# mspm0l1306.net
KiCad netlist of a schematic drawn in EasyEDA Pro
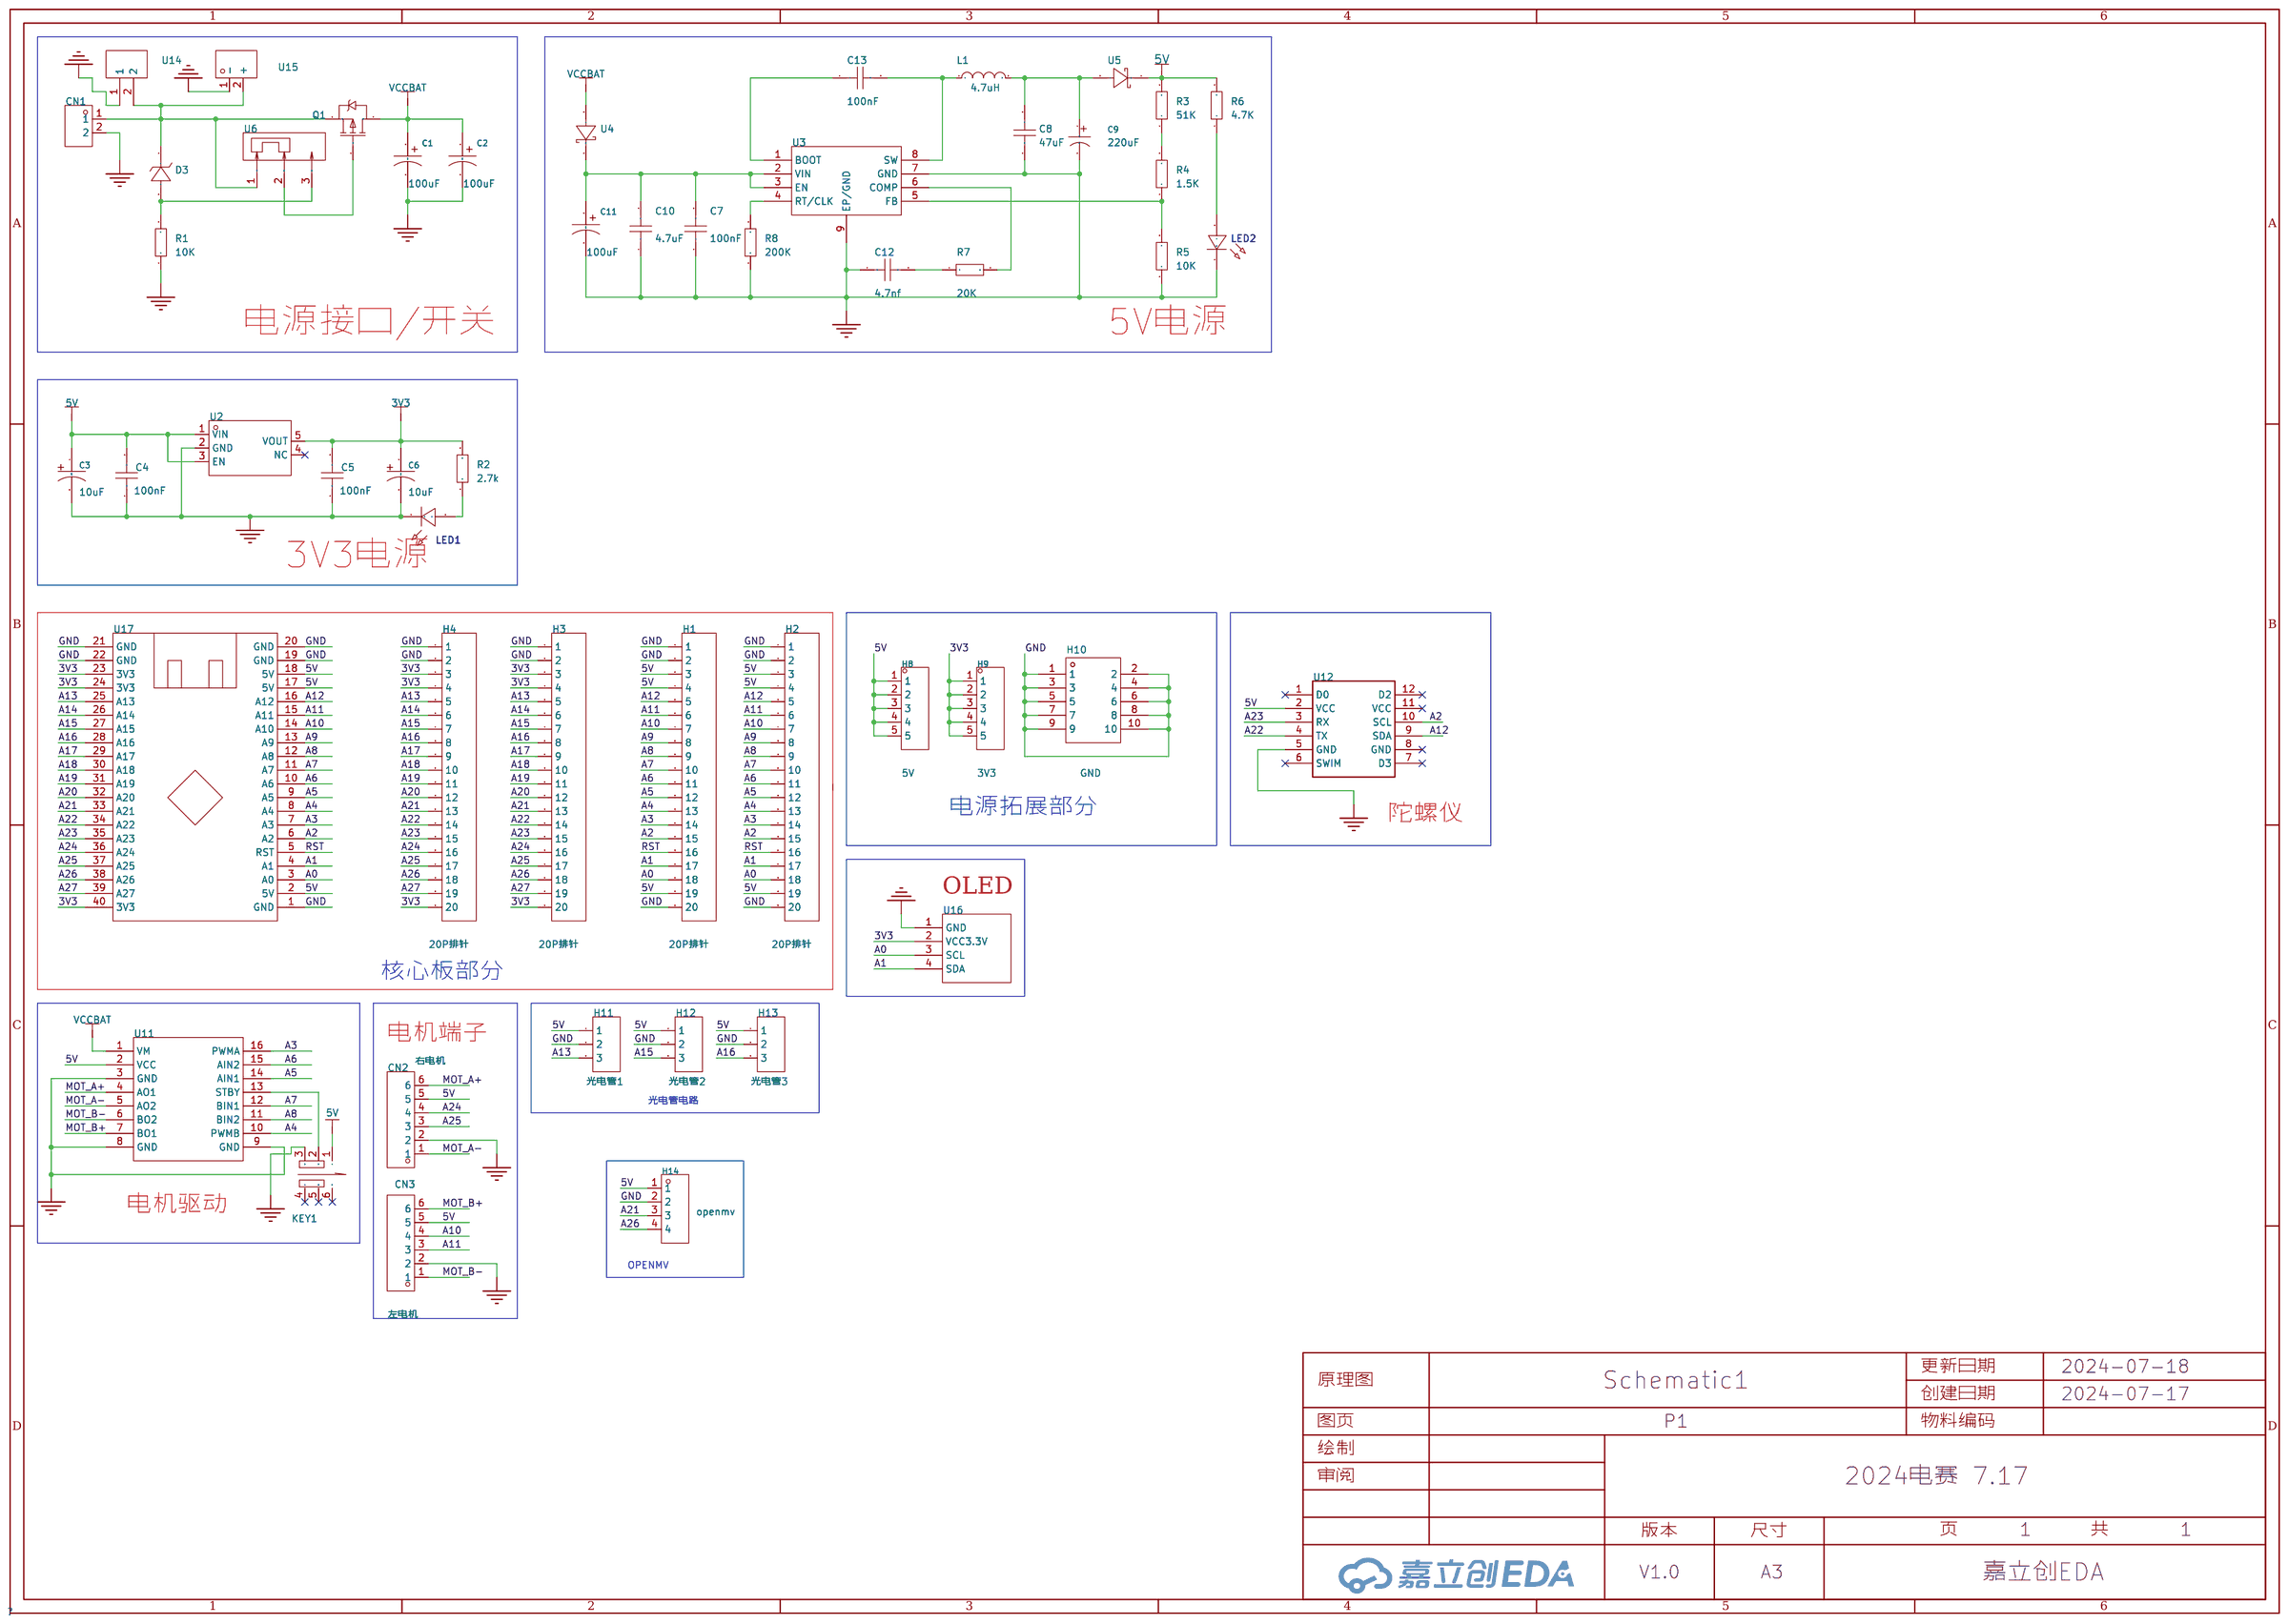
[diagram p0: schematic sheet]

(export (version "E")
  (design (tool "Eeschema 10.0.6"))
  (components
    (comp (ref "C1")
      (value "100uF")
      (fields
        (field (name "Manufacturer Part") "35YXF100MEFCTA8X11.5")
        (field (name "Manufacturer") "rubycon(红宝石)")
      )
      (libsource (lib "easyedapro") (part "35YXF100MEFCTA8X11.5"))
    )
    (comp (ref "C2")
      (value "100uF")
      (fields
        (field (name "Manufacturer Part") "35YXF100MEFCTA8X11.5")
        (field (name "Manufacturer") "rubycon(红宝石)")
      )
      (libsource (lib "easyedapro") (part "35YXF100MEFCTA8X11.5"))
    )
    (comp (ref "C3")
      (value "10uF")
      (footprint "easyedapro:CAP-TH_BD8.0-P3.50-D0.6-FD_1")
      (description "容值:10uF;精度:±20%;额定电压:250V;纹波电流:210mA@100kHz;等效串联电阻:10Ω@100kHz;")
      (fields (field (name "Manufacturer Part") "LKMD0902E100MF") (field (name "Manufacturer") "Ymin(永铭)"))
      (libsource (lib "easyedapro") (part "LKMD0902E100MF"))
    )
    (comp (ref "C4")
      (value "100nF")
      (footprint "easyedapro:C0805")
      (libsource (lib "easyedapro") (part "CapAcitance"))
    )
    (comp (ref "C5")
      (value "100nF")
      (footprint "easyedapro:C0805")
      (libsource (lib "easyedapro") (part "CapAcitance"))
    )
    (comp (ref "C6")
      (value "10uF")
      (footprint "easyedapro:CAP-TH_BD8.0-P3.50-D0.6-FD_1")
      (description "容值:10uF;精度:±20%;额定电压:250V;纹波电流:210mA@100kHz;等效串联电阻:10Ω@100kHz;")
      (fields (field (name "Manufacturer Part") "LKMD0902E100MF") (field (name "Manufacturer") "Ymin(永铭)"))
      (libsource (lib "easyedapro") (part "LKMD0902E100MF"))
    )
    (comp (ref "C7")
      (value "100nF")
      (footprint "easyedapro:C0805")
      (libsource (lib "easyedapro") (part "CapAcitance"))
    )
    (comp (ref "C8")
      (value "47uF")
      (footprint "easyedapro:C0805")
      (libsource (lib "easyedapro") (part "CapAcitance"))
    )
    (comp (ref "C9")
      (value "220uF")
      (fields
        (field (name "Manufacturer Part") "25RX30220M8X11.5")
        (field (name "Manufacturer") "rubycon(红宝石)")
      )
      (libsource (lib "easyedapro") (part "25RX30220M8X11.5"))
    )
    (comp (ref "C10")
      (value "4.7uF")
      (footprint "easyedapro:C0805")
      (libsource (lib "easyedapro") (part "CapAcitance"))
    )
    (comp (ref "C11")
      (value "100uF")
      (fields
        (field (name "Manufacturer Part") "35YXF100MEFCTA8X11.5")
        (field (name "Manufacturer") "rubycon(红宝石)")
      )
      (libsource (lib "easyedapro") (part "35YXF100MEFCTA8X11.5"))
    )
    (comp (ref "C12")
      (value "4.7nf")
      (footprint "easyedapro:C0805")
      (libsource (lib "easyedapro") (part "CapAcitance"))
    )
    (comp (ref "C13")
      (value "100nF")
      (footprint "easyedapro:C0805")
      (libsource (lib "easyedapro") (part "CapAcitance"))
    )
    (comp (ref "CN1")
      (value "XT30U-M")
      (fields (field (name "Manufacturer") "AMASS(艾迈斯)"))
      (libsource (lib "easyedapro") (part "XT30U-M"))
    )
    (comp (ref "CN2")
      (value "右电机")
      (footprint "easyedapro:CONN-TH_XH2.54-6P")
      (fields (field (name "Manufacturer Part") "XH2.54*6P_直插"))
      (libsource (lib "easyedapro") (part "XH2.54*6P_直插"))
    )
    (comp (ref "CN3")
      (value "左电机")
      (footprint "easyedapro:CONN-TH_XH2.54-6P")
      (fields (field (name "Manufacturer Part") "XH2.54*6P_直插"))
      (libsource (lib "easyedapro") (part "XH2.54*6P_直插"))
    )
    (comp (ref "D3")
      (value "BZT52C16")
      (footprint "easyedapro:SOD-123_L2.7-W1.6-LS3.7-RD")
      (description "稳压值(标称值):-;精度:-;功率:500mW;反向电流(Ir):100nA@11.2V;")
      (fields (field (name "Manufacturer") "Slkor(萨科微)"))
      (libsource (lib "easyedapro") (part "BZT52C16_C707145"))
    )
    (comp (ref "H1")
      (value "20P排针")
      (footprint "easyedapro:HDR-TH_20P-P2.54-V-F")
      (libsource (lib "easyedapro") (part "HDR-F_2.54_1x20P"))
    )
    (comp (ref "H2")
      (value "20P排针")
      (footprint "easyedapro:HDR-TH_20P-P2.54-V-F")
      (libsource (lib "easyedapro") (part "HDR-F_2.54_1x20P"))
    )
    (comp (ref "H3")
      (value "20P排针")
      (footprint "easyedapro:HDR-TH_20P-P2.54-V-F")
      (libsource (lib "easyedapro") (part "HDR-F_2.54_1x20P"))
    )
    (comp (ref "H4")
      (value "20P排针")
      (footprint "easyedapro:HDR-TH_20P-P2.54-V-F")
      (libsource (lib "easyedapro") (part "HDR-F_2.54_1x20P"))
    )
    (comp (ref "H8")
      (value "5V")
      (footprint "easyedapro:HDR-TH_5P-P2.54-V-M")
      (libsource (lib "easyedapro") (part "MTP125-1105S1"))
    )
    (comp (ref "H9")
      (value "3V3")
      (footprint "easyedapro:HDR-TH_5P-P2.54-V-M")
      (libsource (lib "easyedapro") (part "MTP125-1105S1"))
    )
    (comp (ref "H10")
      (value "GND")
      (footprint "easyedapro:HDR-TH_10P-P2.54-V-M-R2-C5-S2.54")
      (libsource (lib "easyedapro") (part "HDR-M-2.54_2x5"))
    )
    (comp (ref "H11")
      (value "光电管1")
      (footprint "easyedapro:HDR-F-2.54_1X3")
      (libsource (lib "easyedapro") (part "HDR-F-2.54_1x3"))
    )
    (comp (ref "H12")
      (value "光电管2")
      (footprint "easyedapro:HDR-F-2.54_1X3")
      (libsource (lib "easyedapro") (part "HDR-F-2.54_1x3"))
    )
    (comp (ref "H13")
      (value "光电管3")
      (footprint "easyedapro:HDR-F-2.54_1X3")
      (libsource (lib "easyedapro") (part "HDR-F-2.54_1x3"))
    )
    (comp (ref "H14")
      (value "openmv")
      (footprint "easyedapro:HDR-TH_4P-P2.54-V-F")
      (libsource (lib "easyedapro") (part "2.54-1*4P母"))
    )
    (comp (ref "KEY1")
      (value "自锁开关 5.8Z白灰白260G")
      (footprint "easyedapro:SW-TH_6P-L5.8-W5.8-P2.00-LS4.5-TR")
      (description "耐温260度")
      (libsource (lib "easyedapro") (part "Self-locking switch 5.8ZWhite and white260G"))
    )
    (comp (ref "L1")
      (value "4.7uH")
      (fields (field (name "Manufacturer Part") "PK0810-470MB") (field (name "Manufacturer") "SXN(顺翔诺)"))
      (libsource (lib "easyedapro") (part "PK0810-470MB"))
    )
    (comp (ref "LED1")
      (value "~")
      (footprint "easyedapro:LED_0805")
      (libsource (lib "easyedapro") (part "LED_G"))
    )
    (comp (ref "LED2")
      (value "~")
      (footprint "easyedapro:LED_0805")
      (libsource (lib "easyedapro") (part "LED_G"))
    )
    (comp (ref "Q1")
      (value "HY19P03D")
      (footprint "easyedapro:TO-252-2_L6.6-W6.1-P4.57-LS9.9-TL-CW")
      (fields (field (name "Manufacturer") "HUAYI(华羿微)"))
      (libsource (lib "easyedapro") (part "HY19P03D"))
    )
    (comp (ref "R1") (value "10K") (footprint "easyedapro:R0805") (libsource (lib "easyedapro") (part "电阻")))
    (comp (ref "R2") (value "2.7k") (footprint "easyedapro:R0805") (libsource (lib "easyedapro") (part "电阻")))
    (comp (ref "R3") (value "51K") (footprint "easyedapro:R0805") (libsource (lib "easyedapro") (part "电阻")))
    (comp (ref "R4") (value "1.5K") (footprint "easyedapro:R0805") (libsource (lib "easyedapro") (part "电阻")))
    (comp (ref "R5") (value "10K") (footprint "easyedapro:R0805") (libsource (lib "easyedapro") (part "电阻")))
    (comp (ref "R6") (value "4.7K") (footprint "easyedapro:R0805") (libsource (lib "easyedapro") (part "电阻")))
    (comp (ref "R7") (value "20K") (footprint "easyedapro:R0805") (libsource (lib "easyedapro") (part "电阻")))
    (comp (ref "R8") (value "200K") (footprint "easyedapro:R0805") (libsource (lib "easyedapro") (part "电阻")))
    (comp (ref "U2")
      (value "RT9013-3.3GB")
      (footprint "easyedapro:SOT-23-5_L2.9-W1.6-P0.94-LS2.8-BL")
      (libsource (lib "easyedapro") (part "RT9013-3.3GB"))
    )
    (comp (ref "U3")
      (value "~")
      (footprint "easyedapro:ESOP-8_L4.9-W3.9-P1.27-LS6.0-BL-EP3.1")
      (libsource (lib "easyedapro") (part "SP1N28STER"))
    )
    (comp (ref "U4")
      (value "SS54")
      (footprint "easyedapro:SMA_L4.2-W2.6-LS5.1-RD")
      (libsource (lib "easyedapro") (part "SS54_C9900023219"))
    )
    (comp (ref "U5")
      (value "SS54")
      (footprint "easyedapro:SMA_L4.2-W2.6-LS5.1-RD")
      (libsource (lib "easyedapro") (part "SS54_C9900023219"))
    )
    (comp (ref "U6")
      (value "SS-12D10-G5")
      (footprint "easyedapro:SW-TH_SS-12D10-G050")
      (fields (field (name "Manufacturer") "DEALON(德艺隆)"))
      (libsource (lib "easyedapro") (part "SS-12D10-G5"))
    )
    (comp (ref "U11")
      (value "~")
      (footprint "easyedapro:TB6612")
      (description "STBY/VCC接3.3V\nVM接小于12V")
      (libsource (lib "easyedapro") (part "TB6612模块"))
    )
    (comp (ref "U12")
      (value "MPU6050(JY6X)")
      (footprint "easyedapro:维特陀螺仪")
      (libsource (lib "easyedapro") (part "维特陀螺仪"))
    )
    (comp (ref "U14") (value "~") (footprint "easyedapro:T插头") (libsource (lib "easyedapro") (part "T插头")))
    (comp (ref "U15")
      (value "XT60")
      (footprint "easyedapro:CONN-TH_XT60")
      (description "模型锂电连接器 XT60-M")
      (fields (field (name "Manufacturer") "AMASS(艾迈斯)"))
      (libsource (lib "easyedapro") (part "XT60"))
    )
    (comp (ref "U16") (value "~") (libsource (lib "easyedapro") (part "OLED_4P")))
    (comp (ref "U17")
      (value "~")
      (footprint "easyedapro:MspM0L1306")
      (libsource (lib "easyedapro") (part "MspM0L1306核心板"))
    )
  )
  (nets
    (net (code "1") (name "/A0") (class "Default")
      (node (ref "H1") (pin "18") (pinfunction "18_18") (pintype "input"))
      (node (ref "H2") (pin "18") (pinfunction "18_18") (pintype "input"))
      (node (ref "U16") (pin "3") (pinfunction "SCL_3") (pintype "input"))
      (node (ref "U17") (pin "3") (pinfunction "A0_3") (pintype "input"))
    )
    (net (code "2") (name "/A1") (class "Default")
      (node (ref "H1") (pin "17") (pinfunction "17_17") (pintype "input"))
      (node (ref "H2") (pin "17") (pinfunction "17_17") (pintype "input"))
      (node (ref "U16") (pin "4") (pinfunction "SDA_4") (pintype "input"))
      (node (ref "U17") (pin "4") (pinfunction "A1_4") (pintype "input"))
    )
    (net (code "3") (name "/A2") (class "Default")
      (node (ref "H1") (pin "15") (pinfunction "15_15") (pintype "input"))
      (node (ref "H2") (pin "15") (pinfunction "15_15") (pintype "input"))
      (node (ref "U12") (pin "10") (pinfunction "SCL_10") (pintype "input"))
      (node (ref "U17") (pin "6") (pinfunction "A2_6") (pintype "input"))
    )
    (net (code "4") (name "/A3") (class "Default")
      (node (ref "H1") (pin "14") (pinfunction "14_14") (pintype "input"))
      (node (ref "H2") (pin "14") (pinfunction "14_14") (pintype "input"))
      (node (ref "U11") (pin "16") (pinfunction "PWMA_16") (pintype "input"))
      (node (ref "U17") (pin "7") (pinfunction "A3_7") (pintype "input"))
    )
    (net (code "5") (name "/A4") (class "Default")
      (node (ref "H1") (pin "13") (pinfunction "13_13") (pintype "input"))
      (node (ref "H2") (pin "13") (pinfunction "13_13") (pintype "input"))
      (node (ref "U11") (pin "10") (pinfunction "PWMB_10") (pintype "input"))
      (node (ref "U17") (pin "8") (pinfunction "A4_8") (pintype "input"))
    )
    (net (code "6") (name "/A5") (class "Default")
      (node (ref "H1") (pin "12") (pinfunction "12_12") (pintype "input"))
      (node (ref "H2") (pin "12") (pinfunction "12_12") (pintype "input"))
      (node (ref "U11") (pin "14") (pinfunction "AIN1_14") (pintype "input"))
      (node (ref "U17") (pin "9") (pinfunction "A5_9") (pintype "input"))
    )
    (net (code "7") (name "/A6") (class "Default")
      (node (ref "H1") (pin "11") (pinfunction "11_11") (pintype "input"))
      (node (ref "H2") (pin "11") (pinfunction "11_11") (pintype "input"))
      (node (ref "U11") (pin "15") (pinfunction "AIN2_15") (pintype "input"))
      (node (ref "U17") (pin "10") (pinfunction "A6_10") (pintype "input"))
    )
    (net (code "8") (name "/A7") (class "Default")
      (node (ref "H1") (pin "10") (pinfunction "10_10") (pintype "input"))
      (node (ref "H2") (pin "10") (pinfunction "10_10") (pintype "input"))
      (node (ref "U11") (pin "12") (pinfunction "BIN1_12") (pintype "input"))
      (node (ref "U17") (pin "11") (pinfunction "A7_11") (pintype "input"))
    )
    (net (code "9") (name "/A8") (class "Default")
      (node (ref "H1") (pin "9") (pinfunction "9_9") (pintype "input"))
      (node (ref "H2") (pin "9") (pinfunction "9_9") (pintype "input"))
      (node (ref "U11") (pin "11") (pinfunction "BIN2_11") (pintype "input"))
      (node (ref "U17") (pin "12") (pinfunction "A8_12") (pintype "input"))
    )
    (net (code "10") (name "/A9") (class "Default")
      (node (ref "H1") (pin "8") (pinfunction "8_8") (pintype "input"))
      (node (ref "H2") (pin "8") (pinfunction "8_8") (pintype "input"))
      (node (ref "U17") (pin "13") (pinfunction "A9_13") (pintype "input"))
    )
    (net (code "11") (name "/A10") (class "Default")
      (node (ref "CN3") (pin "4") (pinfunction "4_4") (pintype "input"))
      (node (ref "H1") (pin "7") (pinfunction "7_7") (pintype "input"))
      (node (ref "H2") (pin "7") (pinfunction "7_7") (pintype "input"))
      (node (ref "U17") (pin "14") (pinfunction "A10_14") (pintype "input"))
    )
    (net (code "12") (name "/A11") (class "Default")
      (node (ref "CN3") (pin "3") (pinfunction "3_3") (pintype "input"))
      (node (ref "H1") (pin "6") (pinfunction "6_6") (pintype "input"))
      (node (ref "H2") (pin "6") (pinfunction "6_6") (pintype "input"))
      (node (ref "U17") (pin "15") (pinfunction "A11_15") (pintype "input"))
    )
    (net (code "13") (name "/A12") (class "Default")
      (node (ref "H1") (pin "5") (pinfunction "5_5") (pintype "input"))
      (node (ref "H2") (pin "5") (pinfunction "5_5") (pintype "input"))
      (node (ref "U12") (pin "9") (pinfunction "SDA_9") (pintype "input"))
      (node (ref "U17") (pin "16") (pinfunction "A12_16") (pintype "input"))
    )
    (net (code "14") (name "/A13") (class "Default")
      (node (ref "H11") (pin "3") (pinfunction "3_3") (pintype "input"))
      (node (ref "H3") (pin "5") (pinfunction "5_5") (pintype "input"))
      (node (ref "H4") (pin "5") (pinfunction "5_5") (pintype "input"))
      (node (ref "U17") (pin "25") (pinfunction "A13_25") (pintype "input"))
    )
    (net (code "15") (name "/A14") (class "Default")
      (node (ref "H3") (pin "6") (pinfunction "6_6") (pintype "input"))
      (node (ref "H4") (pin "6") (pinfunction "6_6") (pintype "input"))
      (node (ref "U17") (pin "26") (pinfunction "A14_26") (pintype "input"))
    )
    (net (code "16") (name "/A15") (class "Default")
      (node (ref "H12") (pin "3") (pinfunction "3_3") (pintype "input"))
      (node (ref "H3") (pin "7") (pinfunction "7_7") (pintype "input"))
      (node (ref "H4") (pin "7") (pinfunction "7_7") (pintype "input"))
      (node (ref "U17") (pin "27") (pinfunction "A15_27") (pintype "input"))
    )
    (net (code "17") (name "/A16") (class "Default")
      (node (ref "H13") (pin "3") (pinfunction "3_3") (pintype "input"))
      (node (ref "H3") (pin "8") (pinfunction "8_8") (pintype "input"))
      (node (ref "H4") (pin "8") (pinfunction "8_8") (pintype "input"))
      (node (ref "U17") (pin "28") (pinfunction "A16_28") (pintype "input"))
    )
    (net (code "18") (name "/A17") (class "Default")
      (node (ref "H3") (pin "9") (pinfunction "9_9") (pintype "input"))
      (node (ref "H4") (pin "9") (pinfunction "9_9") (pintype "input"))
      (node (ref "U17") (pin "29") (pinfunction "A17_29") (pintype "input"))
    )
    (net (code "19") (name "/A18") (class "Default")
      (node (ref "H3") (pin "10") (pinfunction "10_10") (pintype "input"))
      (node (ref "H4") (pin "10") (pinfunction "10_10") (pintype "input"))
      (node (ref "U17") (pin "30") (pinfunction "A18_30") (pintype "input"))
    )
    (net (code "20") (name "/A19") (class "Default")
      (node (ref "H3") (pin "11") (pinfunction "11_11") (pintype "input"))
      (node (ref "H4") (pin "11") (pinfunction "11_11") (pintype "input"))
      (node (ref "U17") (pin "31") (pinfunction "A19_31") (pintype "input"))
    )
    (net (code "21") (name "/A20") (class "Default")
      (node (ref "H3") (pin "12") (pinfunction "12_12") (pintype "input"))
      (node (ref "H4") (pin "12") (pinfunction "12_12") (pintype "input"))
      (node (ref "U17") (pin "32") (pinfunction "A20_32") (pintype "input"))
    )
    (net (code "22") (name "/A21") (class "Default")
      (node (ref "H14") (pin "3") (pinfunction "3_3") (pintype "input"))
      (node (ref "H3") (pin "13") (pinfunction "13_13") (pintype "input"))
      (node (ref "H4") (pin "13") (pinfunction "13_13") (pintype "input"))
      (node (ref "U17") (pin "33") (pinfunction "A21_33") (pintype "input"))
    )
    (net (code "23") (name "/A22") (class "Default")
      (node (ref "H3") (pin "14") (pinfunction "14_14") (pintype "input"))
      (node (ref "H4") (pin "14") (pinfunction "14_14") (pintype "input"))
      (node (ref "U12") (pin "4") (pinfunction "TX_4") (pintype "input"))
      (node (ref "U17") (pin "34") (pinfunction "A22_34") (pintype "input"))
    )
    (net (code "24") (name "/A23") (class "Default")
      (node (ref "H3") (pin "15") (pinfunction "15_15") (pintype "input"))
      (node (ref "H4") (pin "15") (pinfunction "15_15") (pintype "input"))
      (node (ref "U12") (pin "3") (pinfunction "RX_3") (pintype "input"))
      (node (ref "U17") (pin "35") (pinfunction "A23_35") (pintype "input"))
    )
    (net (code "25") (name "/A24") (class "Default")
      (node (ref "CN2") (pin "4") (pinfunction "4_4") (pintype "input"))
      (node (ref "H3") (pin "16") (pinfunction "16_16") (pintype "input"))
      (node (ref "H4") (pin "16") (pinfunction "16_16") (pintype "input"))
      (node (ref "U17") (pin "36") (pinfunction "A24_36") (pintype "input"))
    )
    (net (code "26") (name "/A25") (class "Default")
      (node (ref "CN2") (pin "3") (pinfunction "3_3") (pintype "input"))
      (node (ref "H3") (pin "17") (pinfunction "17_17") (pintype "input"))
      (node (ref "H4") (pin "17") (pinfunction "17_17") (pintype "input"))
      (node (ref "U17") (pin "37") (pinfunction "A25_37") (pintype "input"))
    )
    (net (code "27") (name "/A26") (class "Default")
      (node (ref "H14") (pin "4") (pinfunction "4_4") (pintype "input"))
      (node (ref "H3") (pin "18") (pinfunction "18_18") (pintype "input"))
      (node (ref "H4") (pin "18") (pinfunction "18_18") (pintype "input"))
      (node (ref "U17") (pin "38") (pinfunction "A26_38") (pintype "input"))
    )
    (net (code "28") (name "/A27") (class "Default")
      (node (ref "H3") (pin "19") (pinfunction "19_19") (pintype "input"))
      (node (ref "H4") (pin "19") (pinfunction "19_19") (pintype "input"))
      (node (ref "U17") (pin "39") (pinfunction "A27_39") (pintype "input"))
    )
    (net (code "29") (name "/MOT_A+") (class "Default")
      (node (ref "CN2") (pin "6") (pinfunction "6_6") (pintype "input"))
      (node (ref "U11") (pin "4") (pinfunction "AO1_4") (pintype "input"))
    )
    (net (code "30") (name "/MOT_A-") (class "Default")
      (node (ref "CN2") (pin "1") (pinfunction "1_1") (pintype "input"))
      (node (ref "U11") (pin "5") (pinfunction "AO2_5") (pintype "input"))
    )
    (net (code "31") (name "/MOT_B+") (class "Default")
      (node (ref "CN3") (pin "6") (pinfunction "6_6") (pintype "input"))
      (node (ref "U11") (pin "7") (pinfunction "BO1_7") (pintype "input"))
    )
    (net (code "32") (name "/MOT_B-") (class "Default")
      (node (ref "CN3") (pin "1") (pinfunction "1_1") (pintype "input"))
      (node (ref "U11") (pin "6") (pinfunction "BO2_6") (pintype "input"))
    )
    (net (code "33") (name "/RST") (class "Default")
      (node (ref "H1") (pin "16") (pinfunction "16_16") (pintype "input"))
      (node (ref "H2") (pin "16") (pinfunction "16_16") (pintype "input"))
      (node (ref "U17") (pin "5") (pinfunction "RST_5") (pintype "input"))
    )
    (net (code "34") (name "3V3") (class "Default")
      (node (ref "C5") (pin "2") (pinfunction "2_2") (pintype "input"))
      (node (ref "C6") (pin "1") (pinfunction "1_1") (pintype "input"))
      (node (ref "H3") (pin "20") (pinfunction "20_20") (pintype "input"))
      (node (ref "H3") (pin "3") (pinfunction "3_3") (pintype "input"))
      (node (ref "H3") (pin "4") (pinfunction "4_4") (pintype "input"))
      (node (ref "H4") (pin "20") (pinfunction "20_20") (pintype "input"))
      (node (ref "H4") (pin "3") (pinfunction "3_3") (pintype "input"))
      (node (ref "H4") (pin "4") (pinfunction "4_4") (pintype "input"))
      (node (ref "H9") (pin "1") (pinfunction "1_1") (pintype "input"))
      (node (ref "H9") (pin "2") (pinfunction "2_2") (pintype "input"))
      (node (ref "H9") (pin "3") (pinfunction "3_3") (pintype "input"))
      (node (ref "H9") (pin "4") (pinfunction "4_4") (pintype "input"))
      (node (ref "H9") (pin "5") (pinfunction "5_5") (pintype "input"))
      (node (ref "R2") (pin "2") (pinfunction "2_2") (pintype "input"))
      (node (ref "U16") (pin "2") (pinfunction "VCC3.3V_2") (pintype "input"))
      (node (ref "U17") (pin "23") (pinfunction "3V3_23") (pintype "input"))
      (node (ref "U17") (pin "24") (pinfunction "3V3_24") (pintype "input"))
      (node (ref "U17") (pin "40") (pinfunction "3V3_40") (pintype "input"))
      (node (ref "U2") (pin "5") (pinfunction "VOUT_5") (pintype "input"))
    )
    (net (code "35") (name "5V") (class "Default")
      (node (ref "C3") (pin "1") (pinfunction "1_1") (pintype "input"))
      (node (ref "C4") (pin "2") (pinfunction "2_2") (pintype "input"))
      (node (ref "CN2") (pin "5") (pinfunction "5_5") (pintype "input"))
      (node (ref "CN3") (pin "5") (pinfunction "5_5") (pintype "input"))
      (node (ref "H1") (pin "19") (pinfunction "19_19") (pintype "input"))
      (node (ref "H1") (pin "3") (pinfunction "3_3") (pintype "input"))
      (node (ref "H1") (pin "4") (pinfunction "4_4") (pintype "input"))
      (node (ref "H11") (pin "1") (pinfunction "1_1") (pintype "input"))
      (node (ref "H12") (pin "1") (pinfunction "1_1") (pintype "input"))
      (node (ref "H13") (pin "1") (pinfunction "1_1") (pintype "input"))
      (node (ref "H14") (pin "1") (pinfunction "1_1") (pintype "input"))
      (node (ref "H2") (pin "19") (pinfunction "19_19") (pintype "input"))
      (node (ref "H2") (pin "3") (pinfunction "3_3") (pintype "input"))
      (node (ref "H2") (pin "4") (pinfunction "4_4") (pintype "input"))
      (node (ref "H8") (pin "1") (pinfunction "1_1") (pintype "input"))
      (node (ref "H8") (pin "2") (pinfunction "2_2") (pintype "input"))
      (node (ref "H8") (pin "3") (pinfunction "3_3") (pintype "input"))
      (node (ref "H8") (pin "4") (pinfunction "4_4") (pintype "input"))
      (node (ref "H8") (pin "5") (pinfunction "5_5") (pintype "input"))
      (node (ref "KEY1") (pin "1") (pinfunction "1_1") (pintype "input"))
      (node (ref "R3") (pin "2") (pinfunction "2_2") (pintype "input"))
      (node (ref "R6") (pin "2") (pinfunction "2_2") (pintype "input"))
      (node (ref "U11") (pin "2") (pinfunction "VCC_2") (pintype "input"))
      (node (ref "U12") (pin "2") (pinfunction "VCC_2") (pintype "input"))
      (node (ref "U17") (pin "17") (pinfunction "5V_17") (pintype "input"))
      (node (ref "U17") (pin "18") (pinfunction "5V_18") (pintype "input"))
      (node (ref "U17") (pin "2") (pinfunction "5V_2") (pintype "input"))
      (node (ref "U2") (pin "1") (pinfunction "VIN_1") (pintype "input"))
      (node (ref "U2") (pin "3") (pinfunction "EN_3") (pintype "input"))
      (node (ref "U5") (pin "1") (pinfunction "C_1") (pintype "input"))
    )
    (net (code "36") (name "GND") (class "Default")
      (node (ref "C1") (pin "2") (pinfunction "2_2") (pintype "unspecified"))
      (node (ref "C10") (pin "1") (pinfunction "1_1") (pintype "input"))
      (node (ref "C11") (pin "2") (pinfunction "2_2") (pintype "unspecified"))
      (node (ref "C12") (pin "1") (pinfunction "1_1") (pintype "input"))
      (node (ref "C2") (pin "2") (pinfunction "2_2") (pintype "unspecified"))
      (node (ref "C3") (pin "2") (pinfunction "2_2") (pintype "input"))
      (node (ref "C4") (pin "1") (pinfunction "1_1") (pintype "input"))
      (node (ref "C5") (pin "1") (pinfunction "1_1") (pintype "input"))
      (node (ref "C6") (pin "2") (pinfunction "2_2") (pintype "input"))
      (node (ref "C7") (pin "1") (pinfunction "1_1") (pintype "input"))
      (node (ref "C8") (pin "1") (pinfunction "1_1") (pintype "input"))
      (node (ref "C9") (pin "2") (pinfunction "2_2") (pintype "input"))
      (node (ref "CN1") (pin "2") (pinfunction "2_2") (pintype "unspecified"))
      (node (ref "CN2") (pin "2") (pinfunction "2_2") (pintype "input"))
      (node (ref "CN3") (pin "2") (pinfunction "2_2") (pintype "input"))
      (node (ref "H1") (pin "1") (pinfunction "1_1") (pintype "input"))
      (node (ref "H1") (pin "2") (pinfunction "2_2") (pintype "input"))
      (node (ref "H1") (pin "20") (pinfunction "20_20") (pintype "input"))
      (node (ref "H10") (pin "1") (pinfunction "1_1") (pintype "input"))
      (node (ref "H10") (pin "10") (pinfunction "10_10") (pintype "input"))
      (node (ref "H10") (pin "2") (pinfunction "2_2") (pintype "input"))
      (node (ref "H10") (pin "3") (pinfunction "3_3") (pintype "input"))
      (node (ref "H10") (pin "4") (pinfunction "4_4") (pintype "input"))
      (node (ref "H10") (pin "5") (pinfunction "5_5") (pintype "input"))
      (node (ref "H10") (pin "6") (pinfunction "6_6") (pintype "input"))
      (node (ref "H10") (pin "7") (pinfunction "7_7") (pintype "input"))
      (node (ref "H10") (pin "8") (pinfunction "8_8") (pintype "input"))
      (node (ref "H10") (pin "9") (pinfunction "9_9") (pintype "input"))
      (node (ref "H11") (pin "2") (pinfunction "2_2") (pintype "input"))
      (node (ref "H12") (pin "2") (pinfunction "2_2") (pintype "input"))
      (node (ref "H13") (pin "2") (pinfunction "2_2") (pintype "input"))
      (node (ref "H14") (pin "2") (pinfunction "2_2") (pintype "input"))
      (node (ref "H2") (pin "1") (pinfunction "1_1") (pintype "input"))
      (node (ref "H2") (pin "2") (pinfunction "2_2") (pintype "input"))
      (node (ref "H2") (pin "20") (pinfunction "20_20") (pintype "input"))
      (node (ref "H3") (pin "1") (pinfunction "1_1") (pintype "input"))
      (node (ref "H3") (pin "2") (pinfunction "2_2") (pintype "input"))
      (node (ref "H4") (pin "1") (pinfunction "1_1") (pintype "input"))
      (node (ref "H4") (pin "2") (pinfunction "2_2") (pintype "input"))
      (node (ref "KEY1") (pin "3") (pinfunction "3_3") (pintype "input"))
      (node (ref "LED1") (pin "1") (pinfunction "C_1") (pintype "input"))
      (node (ref "LED2") (pin "1") (pinfunction "C_1") (pintype "input"))
      (node (ref "R1") (pin "1") (pinfunction "1_1") (pintype "input"))
      (node (ref "R5") (pin "1") (pinfunction "1_1") (pintype "input"))
      (node (ref "R8") (pin "1") (pinfunction "1_1") (pintype "input"))
      (node (ref "U11") (pin "3") (pinfunction "GND_3") (pintype "input"))
      (node (ref "U11") (pin "8") (pinfunction "GND_8") (pintype "input"))
      (node (ref "U11") (pin "9") (pinfunction "GND_9") (pintype "input"))
      (node (ref "U12") (pin "5") (pinfunction "GND_5") (pintype "input"))
      (node (ref "U14") (pin "1") (pinfunction "1_1") (pintype "input"))
      (node (ref "U15") (pin "1") (pinfunction "-_1") (pintype "input"))
      (node (ref "U16") (pin "1") (pinfunction "GND_1") (pintype "input"))
      (node (ref "U17") (pin "1") (pinfunction "GND_1") (pintype "input"))
      (node (ref "U17") (pin "19") (pinfunction "GND_19") (pintype "input"))
      (node (ref "U17") (pin "20") (pinfunction "GND_20") (pintype "input"))
      (node (ref "U17") (pin "21") (pinfunction "GND_21") (pintype "input"))
      (node (ref "U17") (pin "22") (pinfunction "GND_22") (pintype "input"))
      (node (ref "U2") (pin "2") (pinfunction "GND_2") (pintype "input"))
      (node (ref "U3") (pin "7") (pinfunction "GND_7") (pintype "input"))
      (node (ref "U3") (pin "9") (pinfunction "EP/GND_9") (pintype "input"))
    )
    (net (code "37") (name "Net-(C12-Pad2)") (class "Default")
      (node (ref "C12") (pin "2") (pinfunction "2_2") (pintype "input"))
      (node (ref "R7") (pin "1") (pinfunction "1_1") (pintype "input"))
    )
    (net (code "38") (name "Net-(D3-A)") (class "Default")
      (node (ref "D3") (pin "2") (pinfunction "A_2") (pintype "input"))
      (node (ref "R1") (pin "2") (pinfunction "2_2") (pintype "input"))
      (node (ref "U6") (pin "3") (pinfunction "3_3") (pintype "input"))
    )
    (net (code "39") (name "Net-(D3-K)") (class "Default")
      (node (ref "CN1") (pin "1") (pinfunction "1_1") (pintype "unspecified"))
      (node (ref "D3") (pin "1") (pinfunction "K_1") (pintype "input"))
      (node (ref "Q1") (pin "3") (pinfunction "S_3") (pintype "input"))
      (node (ref "U14") (pin "2") (pinfunction "2_2") (pintype "input"))
      (node (ref "U15") (pin "2") (pinfunction "+_2") (pintype "input"))
      (node (ref "U6") (pin "1") (pinfunction "1_1") (pintype "input"))
    )
    (net (code "40") (name "Net-(LED1-A)") (class "Default")
      (node (ref "LED1") (pin "2") (pinfunction "A_2") (pintype "input"))
      (node (ref "R2") (pin "1") (pinfunction "1_1") (pintype "input"))
    )
    (net (code "41") (name "Net-(LED2-A)") (class "Default")
      (node (ref "LED2") (pin "2") (pinfunction "A_2") (pintype "input"))
      (node (ref "R6") (pin "1") (pinfunction "1_1") (pintype "input"))
    )
    (net (code "42") (name "Net-(Q1-G)") (class "Default")
      (node (ref "Q1") (pin "1") (pinfunction "G_1") (pintype "input"))
      (node (ref "U6") (pin "2") (pinfunction "2_2") (pintype "input"))
    )
    (net (code "43") (name "Net-(R3-Pad1)") (class "Default")
      (node (ref "R3") (pin "1") (pinfunction "1_1") (pintype "input"))
      (node (ref "R4") (pin "2") (pinfunction "2_2") (pintype "input"))
    )
    (net (code "44") (name "Net-(U3-BOOT)") (class "Default")
      (node (ref "C13") (pin "1") (pinfunction "1_1") (pintype "input"))
      (node (ref "U3") (pin "1") (pinfunction "BOOT_1") (pintype "input"))
    )
    (net (code "45") (name "Net-(U3-COMP)") (class "Default")
      (node (ref "R7") (pin "2") (pinfunction "2_2") (pintype "input"))
      (node (ref "U3") (pin "6") (pinfunction "COMP_6") (pintype "input"))
    )
    (net (code "46") (name "Net-(U3-EN)") (class "Default")
      (node (ref "C10") (pin "2") (pinfunction "2_2") (pintype "input"))
      (node (ref "C11") (pin "1") (pinfunction "1_1") (pintype "unspecified"))
      (node (ref "C7") (pin "2") (pinfunction "2_2") (pintype "input"))
      (node (ref "U3") (pin "2") (pinfunction "VIN_2") (pintype "input"))
      (node (ref "U3") (pin "3") (pinfunction "EN_3") (pintype "input"))
      (node (ref "U4") (pin "1") (pinfunction "C_1") (pintype "input"))
    )
    (net (code "47") (name "Net-(U3-FB)") (class "Default")
      (node (ref "R4") (pin "1") (pinfunction "1_1") (pintype "input"))
      (node (ref "R5") (pin "2") (pinfunction "2_2") (pintype "input"))
      (node (ref "U3") (pin "5") (pinfunction "FB_5") (pintype "input"))
    )
    (net (code "48") (name "Net-(U3-RT{slash}CLK)") (class "Default")
      (node (ref "R8") (pin "2") (pinfunction "2_2") (pintype "input"))
      (node (ref "U3") (pin "4") (pinfunction "RT/CLK_4") (pintype "input"))
    )
    (net (code "49") (name "Net-(U3-SW)") (class "Default")
      (node (ref "C13") (pin "2") (pinfunction "2_2") (pintype "input"))
      (node (ref "L1") (pin "1") (pinfunction "1_1") (pintype "unspecified"))
      (node (ref "U3") (pin "8") (pinfunction "SW_8") (pintype "input"))
    )
    (net (code "50") (name "Net-(U5-A)") (class "Default")
      (node (ref "C8") (pin "2") (pinfunction "2_2") (pintype "input"))
      (node (ref "C9") (pin "1") (pinfunction "1_1") (pintype "input"))
      (node (ref "L1") (pin "2") (pinfunction "2_2") (pintype "unspecified"))
      (node (ref "U5") (pin "2") (pinfunction "A_2") (pintype "input"))
    )
    (net (code "51") (name "Net-(U11-STBY)") (class "Default")
      (node (ref "KEY1") (pin "2") (pinfunction "2_2") (pintype "input"))
      (node (ref "U11") (pin "13") (pinfunction "STBY_13") (pintype "input"))
    )
    (net (code "52") (name "VCCBAT") (class "Default")
      (node (ref "C1") (pin "1") (pinfunction "1_1") (pintype "unspecified"))
      (node (ref "C2") (pin "1") (pinfunction "1_1") (pintype "unspecified"))
      (node (ref "Q1") (pin "2") (pinfunction "D_2") (pintype "input"))
      (node (ref "U11") (pin "1") (pinfunction "VM_1") (pintype "input"))
      (node (ref "U4") (pin "2") (pinfunction "A_2") (pintype "input"))
    )
    (net (code "53") (name "unconnected-(KEY1-Pad4)") (class "Default")
      (node (ref "KEY1") (pin "4") (pinfunction "4_4") (pintype "input+no_connect"))
    )
    (net (code "54") (name "unconnected-(KEY1-Pad5)") (class "Default")
      (node (ref "KEY1") (pin "5") (pinfunction "5_5") (pintype "input+no_connect"))
    )
    (net (code "55") (name "unconnected-(KEY1-Pad6)") (class "Default")
      (node (ref "KEY1") (pin "6") (pinfunction "6_6") (pintype "input+no_connect"))
    )
    (net (code "56") (name "unconnected-(U2-NC-Pad4)") (class "Default")
      (node (ref "U2") (pin "4") (pinfunction "NC_4") (pintype "input+no_connect"))
    )
    (net (code "57") (name "unconnected-(U12-D0-Pad1)") (class "Default")
      (node (ref "U12") (pin "1") (pinfunction "D0_1") (pintype "input+no_connect"))
    )
    (net (code "58") (name "unconnected-(U12-D2-Pad12)") (class "Default")
      (node (ref "U12") (pin "12") (pinfunction "D2_12") (pintype "input+no_connect"))
    )
    (net (code "59") (name "unconnected-(U12-D3-Pad7)") (class "Default")
      (node (ref "U12") (pin "7") (pinfunction "D3_7") (pintype "input+no_connect"))
    )
    (net (code "60") (name "unconnected-(U12-GND-Pad8)") (class "Default")
      (node (ref "U12") (pin "8") (pinfunction "GND_8") (pintype "input+no_connect"))
    )
    (net (code "61") (name "unconnected-(U12-SWIM-Pad6)") (class "Default")
      (node (ref "U12") (pin "6") (pinfunction "SWIM_6") (pintype "input+no_connect"))
    )
    (net (code "62") (name "unconnected-(U12-VCC-Pad11)") (class "Default")
      (node (ref "U12") (pin "11") (pinfunction "VCC_11") (pintype "input+no_connect"))
    )
  )
)
